# Arduino-Pro-Mini.net
KiCad netlist of a schematic drawn in EAGLE
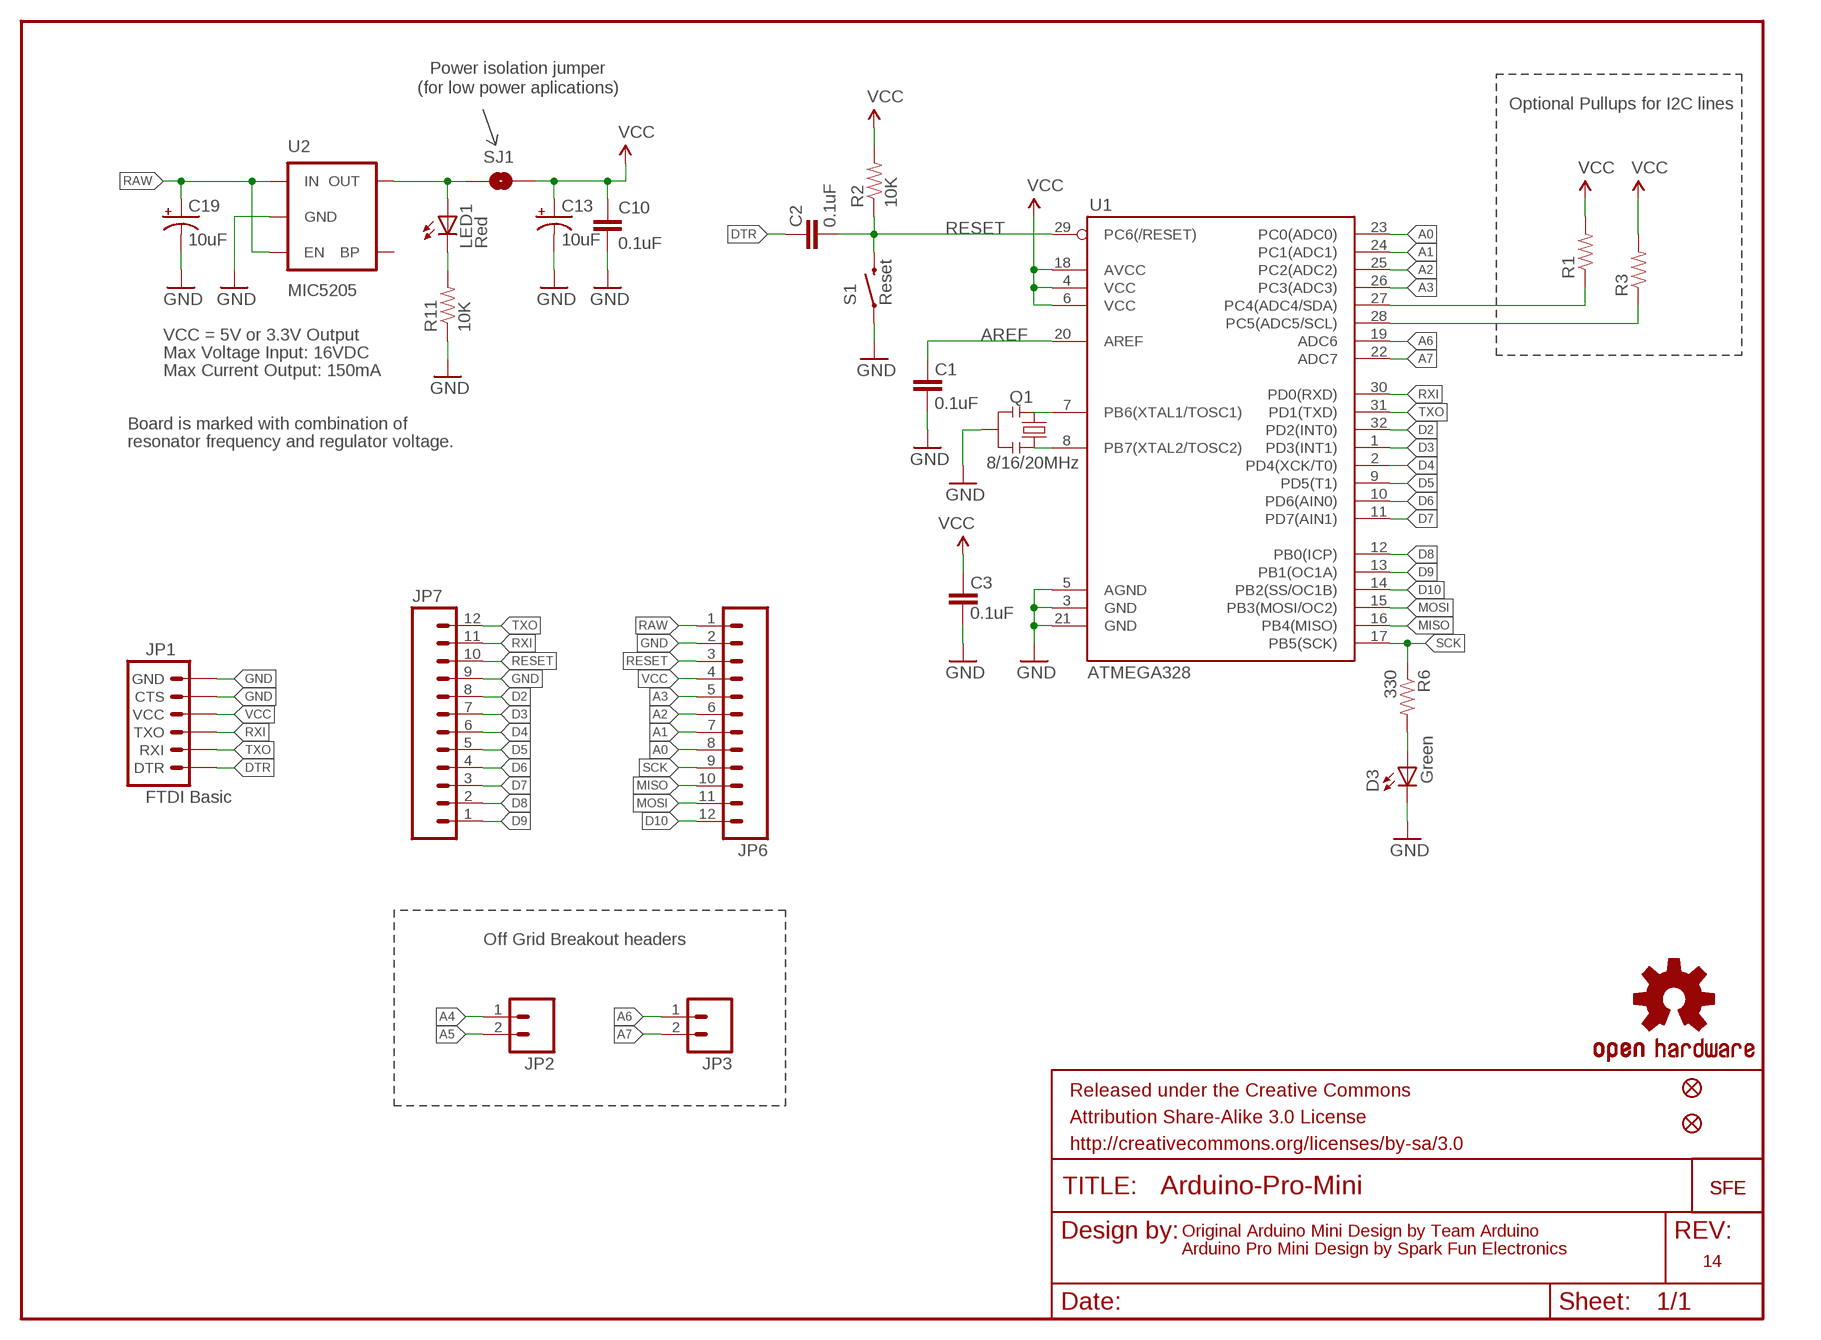
[diagram p0: schematic, sheet 1]

(export (version "E")
  (design (tool "Eeschema 10.0.6"))
  (components
    (comp (ref "C1")
      (value "0.1uF")
      (footprint "eagle-import:0603-CAP")
      (libsource (lib "eagle-import") (part "CAP0603-CAP"))
    )
    (comp (ref "C2")
      (value "0.1uF")
      (footprint "eagle-import:0603-CAP")
      (libsource (lib "eagle-import") (part "CAP0603-CAP"))
    )
    (comp (ref "C3")
      (value "0.1uF")
      (footprint "eagle-import:0603-CAP")
      (libsource (lib "eagle-import") (part "CAP0603-CAP"))
    )
    (comp (ref "C10")
      (value "0.1uF")
      (footprint "eagle-import:0603-CAP")
      (libsource (lib "eagle-import") (part "CAP0603-CAP"))
    )
    (comp (ref "C13")
      (value "10uF")
      (footprint "eagle-import:EIA3216")
      (libsource (lib "eagle-import") (part "CAP_POL1206"))
    )
    (comp (ref "C19")
      (value "10uF")
      (footprint "eagle-import:EIA3216")
      (libsource (lib "eagle-import") (part "CAP_POL1206"))
    )
    (comp (ref "D3")
      (value "Green")
      (footprint "eagle-import:0603-LED-ALT1")
      (libsource (lib "eagle-import") (part "LED"))
    )
    (comp (ref "FRAME1")
      (value "FRAME-LETTER")
      (footprint "eagle-import:CREATIVE_COMMONS")
      (libsource (lib "eagle-import") (part "FRAME-LETTER"))
    )
    (comp (ref "JP1")
      (value "FTDI Basic")
      (footprint "eagle-import:1X06")
      (libsource (lib "eagle-import") (part "ARDUINO_SERIAL_PROGRAMPTH"))
    )
    (comp (ref "JP2")
      (value "M02PTH")
      (footprint "eagle-import:1X02")
      (libsource (lib "eagle-import") (part "M02PTH"))
    )
    (comp (ref "JP3")
      (value "M02PTH")
      (footprint "eagle-import:1X02")
      (libsource (lib "eagle-import") (part "M02PTH"))
    )
    (comp (ref "JP5")
      (value "FIDUCIALUFIDUCIAL")
      (footprint "eagle-import:MICRO-FIDUCIAL")
      (libsource (lib "eagle-import") (part "FIDUCIALUFIDUCIAL"))
    )
    (comp (ref "JP6")
      (value "M12PTH")
      (footprint "eagle-import:1X12")
      (libsource (lib "eagle-import") (part "M12PTH"))
    )
    (comp (ref "JP7")
      (value "M12PTH")
      (footprint "eagle-import:1X12")
      (libsource (lib "eagle-import") (part "M12PTH"))
    )
    (comp (ref "JP8")
      (value "FIDUCIALUFIDUCIAL")
      (footprint "eagle-import:MICRO-FIDUCIAL")
      (libsource (lib "eagle-import") (part "FIDUCIALUFIDUCIAL"))
    )
    (comp (ref "LED1")
      (value "Red")
      (footprint "eagle-import:0603-LED-ALT1")
      (libsource (lib "eagle-import") (part "LED"))
    )
    (comp (ref "Q1")
      (value "8/16/20MHz")
      (footprint "eagle-import:RESONATOR-SMD-1_1")
      (libsource (lib "eagle-import") (part "RESONATOR1{colon}1"))
    )
    (comp (ref "R1")
      (value "RESISTOR0603-RES")
      (footprint "eagle-import:0603-RES")
      (libsource (lib "eagle-import") (part "RESISTOR0603-RES"))
    )
    (comp (ref "R2")
      (value "10K")
      (footprint "eagle-import:0603-RES")
      (libsource (lib "eagle-import") (part "RESISTOR0603-RES"))
    )
    (comp (ref "R3")
      (value "RESISTOR0603-RES")
      (footprint "eagle-import:0603-RES")
      (libsource (lib "eagle-import") (part "RESISTOR0603-RES"))
    )
    (comp (ref "R6")
      (value "330")
      (footprint "eagle-import:0603-RES")
      (libsource (lib "eagle-import") (part "RESISTOR0603-RES"))
    )
    (comp (ref "R11")
      (value "10K")
      (footprint "eagle-import:0603-RES")
      (libsource (lib "eagle-import") (part "RESISTOR0603-RES"))
    )
    (comp (ref "S1")
      (value "Reset")
      (footprint "eagle-import:TACTILE-SWITCH-SMD-ALT01")
      (libsource (lib "eagle-import") (part "SWITCH-MOMENTARY-2SMD-ALT01"))
    )
    (comp (ref "SJ1")
      (value "SOLDERJUMPERNC")
      (footprint "eagle-import:SJ_2S")
      (libsource (lib "eagle-import") (part "SOLDERJUMPERNC"))
    )
    (comp (ref "U$1")
      (value "LOGO-SFESK")
      (footprint "eagle-import:SFE-LOGO-FLAME")
      (libsource (lib "eagle-import") (part "LOGO-SFESK"))
    )
    (comp (ref "U$3")
      (value "OSHW-LOGOS")
      (footprint "eagle-import:OSHW-LOGO-S")
      (libsource (lib "eagle-import") (part "OSHW-LOGOS"))
    )
    (comp (ref "U$11")
      (value "LOGO-SFENEW")
      (footprint "eagle-import:SFE-NEW-WEBLOGO")
      (libsource (lib "eagle-import") (part "LOGO-SFENEW"))
    )
    (comp (ref "U1")
      (value "ATMEGA328")
      (footprint "eagle-import:TQFP32-08")
      (libsource (lib "eagle-import") (part "ATMEGA168"))
    )
    (comp (ref "U2")
      (value "MIC5205")
      (footprint "eagle-import:SOT23-5")
      (libsource (lib "eagle-import") (part "V_REG_LDOSMD"))
    )
  )
  (nets
    (net (code "1") (name "/AREF") (class "Default")
      (node (ref "C1") (pin "2") (pinfunction "2_2") (pintype "passive"))
      (node (ref "U1") (pin "20") (pinfunction "AREF_20") (pintype "bidirectional"))
    )
    (net (code "2") (name "A0") (class "Default")
      (node (ref "JP6") (pin "8") (pinfunction "8_8") (pintype "passive"))
      (node (ref "U1") (pin "23") (pinfunction "PC0(ADC0)_23") (pintype "bidirectional"))
    )
    (net (code "3") (name "A1") (class "Default")
      (node (ref "JP6") (pin "7") (pinfunction "7_7") (pintype "passive"))
      (node (ref "U1") (pin "24") (pinfunction "PC1(ADC1)_24") (pintype "bidirectional"))
    )
    (net (code "4") (name "A2") (class "Default")
      (node (ref "JP6") (pin "6") (pinfunction "6_6") (pintype "passive"))
      (node (ref "U1") (pin "25") (pinfunction "PC2(ADC2)_25") (pintype "bidirectional"))
    )
    (net (code "5") (name "A3") (class "Default")
      (node (ref "JP6") (pin "5") (pinfunction "5_5") (pintype "passive"))
      (node (ref "U1") (pin "26") (pinfunction "PC3(ADC3)_26") (pintype "bidirectional"))
    )
    (net (code "6") (name "A4") (class "Default")
      (node (ref "JP2") (pin "1") (pinfunction "1_1") (pintype "passive"))
      (node (ref "R1") (pin "1") (pinfunction "1_1") (pintype "passive"))
      (node (ref "U1") (pin "27") (pinfunction "PC4(ADC4/SDA)_27") (pintype "bidirectional"))
    )
    (net (code "7") (name "A5") (class "Default")
      (node (ref "JP2") (pin "2") (pinfunction "2_2") (pintype "passive"))
      (node (ref "R3") (pin "1") (pinfunction "1_1") (pintype "passive"))
      (node (ref "U1") (pin "28") (pinfunction "PC5(ADC5/SCL)_28") (pintype "bidirectional"))
    )
    (net (code "8") (name "A6") (class "Default")
      (node (ref "JP3") (pin "1") (pinfunction "1_1") (pintype "passive"))
      (node (ref "U1") (pin "19") (pinfunction "ADC6_19") (pintype "bidirectional"))
    )
    (net (code "9") (name "A7") (class "Default")
      (node (ref "JP3") (pin "2") (pinfunction "2_2") (pintype "passive"))
      (node (ref "U1") (pin "22") (pinfunction "ADC7_22") (pintype "bidirectional"))
    )
    (net (code "10") (name "D2") (class "Default")
      (node (ref "JP7") (pin "8") (pinfunction "8_8") (pintype "passive"))
      (node (ref "U1") (pin "32") (pinfunction "PD2(INT0)_32") (pintype "bidirectional"))
    )
    (net (code "11") (name "D3") (class "Default")
      (node (ref "JP7") (pin "7") (pinfunction "7_7") (pintype "passive"))
      (node (ref "U1") (pin "1") (pinfunction "PD3(INT1)_1") (pintype "bidirectional"))
    )
    (net (code "12") (name "D4") (class "Default")
      (node (ref "JP7") (pin "6") (pinfunction "6_6") (pintype "passive"))
      (node (ref "U1") (pin "2") (pinfunction "PD4(XCK/T0)_2") (pintype "bidirectional"))
    )
    (net (code "13") (name "D5") (class "Default")
      (node (ref "JP7") (pin "5") (pinfunction "5_5") (pintype "passive"))
      (node (ref "U1") (pin "9") (pinfunction "PD5(T1)_9") (pintype "bidirectional"))
    )
    (net (code "14") (name "D6") (class "Default")
      (node (ref "JP7") (pin "4") (pinfunction "4_4") (pintype "passive"))
      (node (ref "U1") (pin "10") (pinfunction "PD6(AIN0)_10") (pintype "bidirectional"))
    )
    (net (code "15") (name "D7") (class "Default")
      (node (ref "JP7") (pin "3") (pinfunction "3_3") (pintype "passive"))
      (node (ref "U1") (pin "11") (pinfunction "PD7(AIN1)_11") (pintype "bidirectional"))
    )
    (net (code "16") (name "D8") (class "Default")
      (node (ref "JP7") (pin "2") (pinfunction "2_2") (pintype "passive"))
      (node (ref "U1") (pin "12") (pinfunction "PB0(ICP)_12") (pintype "bidirectional"))
    )
    (net (code "17") (name "D9") (class "Default")
      (node (ref "JP7") (pin "1") (pinfunction "1_1") (pintype "passive"))
      (node (ref "U1") (pin "13") (pinfunction "PB1(OC1A)_13") (pintype "bidirectional"))
    )
    (net (code "18") (name "D10") (class "Default")
      (node (ref "JP6") (pin "12") (pinfunction "12_12") (pintype "passive"))
      (node (ref "U1") (pin "14") (pinfunction "PB2(SS/OC1B)_14") (pintype "bidirectional"))
    )
    (net (code "19") (name "DTR") (class "Default")
      (node (ref "C2") (pin "2") (pinfunction "2_2") (pintype "passive"))
      (node (ref "JP1") (pin "1") (pinfunction "DTR_1") (pintype "passive"))
    )
    (net (code "20") (name "GND") (class "Default")
      (node (ref "C1") (pin "1") (pinfunction "1_1") (pintype "passive"))
      (node (ref "C10") (pin "2") (pinfunction "2_2") (pintype "passive"))
      (node (ref "C13") (pin "C") (pinfunction "-_C") (pintype "passive"))
      (node (ref "C19") (pin "C") (pinfunction "-_C") (pintype "passive"))
      (node (ref "C3") (pin "1") (pinfunction "1_1") (pintype "passive"))
      (node (ref "D3") (pin "C") (pinfunction "C_C") (pintype "passive"))
      (node (ref "JP1") (pin "5") (pinfunction "CTS_5") (pintype "passive"))
      (node (ref "JP1") (pin "6") (pinfunction "GND_6") (pintype "passive"))
      (node (ref "JP6") (pin "2") (pinfunction "2_2") (pintype "passive"))
      (node (ref "JP7") (pin "9") (pinfunction "9_9") (pintype "passive"))
      (node (ref "Q1") (pin "2") (pinfunction "2_2") (pintype "passive"))
      (node (ref "R11") (pin "1") (pinfunction "1_1") (pintype "passive"))
      (node (ref "S1") (pin "1") (pinfunction "1_1") (pintype "passive"))
      (node (ref "S1") (pin "2") (pinfunction "1_2") (pintype "passive"))
      (node (ref "U1") (pin "21") (pinfunction "GND_21") (pintype "bidirectional"))
      (node (ref "U1") (pin "3") (pinfunction "GND_3") (pintype "bidirectional"))
      (node (ref "U1") (pin "5") (pinfunction "AGND_5") (pintype "bidirectional"))
      (node (ref "U2") (pin "2") (pinfunction "GND_2") (pintype "input"))
    )
    (net (code "21") (name "MISO") (class "Default")
      (node (ref "JP6") (pin "10") (pinfunction "10_10") (pintype "passive"))
      (node (ref "U1") (pin "16") (pinfunction "PB4(MISO)_16") (pintype "bidirectional"))
    )
    (net (code "22") (name "MOSI") (class "Default")
      (node (ref "JP6") (pin "11") (pinfunction "11_11") (pintype "passive"))
      (node (ref "U1") (pin "15") (pinfunction "PB3(MOSI/OC2)_15") (pintype "bidirectional"))
    )
    (net (code "23") (name "Net-(D3-PadA)") (class "Default")
      (node (ref "D3") (pin "A") (pinfunction "A_A") (pintype "passive"))
      (node (ref "R6") (pin "2") (pinfunction "2_2") (pintype "passive"))
    )
    (net (code "24") (name "Net-(LED1-PadC)") (class "Default")
      (node (ref "LED1") (pin "C") (pinfunction "C_C") (pintype "passive"))
      (node (ref "R11") (pin "2") (pinfunction "2_2") (pintype "passive"))
    )
    (net (code "25") (name "Net-(U1-PB6(XTAL1{slash}TOSC1))") (class "Default")
      (node (ref "Q1") (pin "1") (pinfunction "1_1") (pintype "passive"))
      (node (ref "U1") (pin "7") (pinfunction "PB6(XTAL1/TOSC1)_7") (pintype "bidirectional"))
    )
    (net (code "26") (name "Net-(U1-PB7(XTAL2{slash}TOSC2))") (class "Default")
      (node (ref "Q1") (pin "3") (pinfunction "3_3") (pintype "passive"))
      (node (ref "U1") (pin "8") (pinfunction "PB7(XTAL2/TOSC2)_8") (pintype "bidirectional"))
    )
    (net (code "27") (name "Net-(U2-OUT)") (class "Default")
      (node (ref "LED1") (pin "A") (pinfunction "A_A") (pintype "passive"))
      (node (ref "SJ1") (pin "1") (pinfunction "1_1") (pintype "passive"))
      (node (ref "U2") (pin "5") (pinfunction "OUT_5") (pintype "passive"))
    )
    (net (code "28") (name "RAW") (class "Default")
      (node (ref "C19") (pin "A") (pinfunction "+_A") (pintype "passive"))
      (node (ref "JP6") (pin "1") (pinfunction "1_1") (pintype "passive"))
      (node (ref "U2") (pin "1") (pinfunction "IN_1") (pintype "input"))
      (node (ref "U2") (pin "3") (pinfunction "EN_3") (pintype "input"))
    )
    (net (code "29") (name "RESET") (class "Default")
      (node (ref "C2") (pin "1") (pinfunction "1_1") (pintype "passive"))
      (node (ref "JP6") (pin "3") (pinfunction "3_3") (pintype "passive"))
      (node (ref "JP7") (pin "10") (pinfunction "10_10") (pintype "passive"))
      (node (ref "R2") (pin "1") (pinfunction "1_1") (pintype "passive"))
      (node (ref "S1") (pin "3") (pinfunction "2_3") (pintype "passive"))
      (node (ref "S1") (pin "4") (pinfunction "2_4") (pintype "passive"))
      (node (ref "U1") (pin "29") (pinfunction "PC6(/RESET)_29") (pintype "bidirectional"))
    )
    (net (code "30") (name "RXI") (class "Default")
      (node (ref "JP1") (pin "3") (pinfunction "TXO_3") (pintype "passive"))
      (node (ref "JP7") (pin "11") (pinfunction "11_11") (pintype "passive"))
      (node (ref "U1") (pin "30") (pinfunction "PD0(RXD)_30") (pintype "bidirectional"))
    )
    (net (code "31") (name "SCK") (class "Default")
      (node (ref "JP6") (pin "9") (pinfunction "9_9") (pintype "passive"))
      (node (ref "R6") (pin "1") (pinfunction "1_1") (pintype "passive"))
      (node (ref "U1") (pin "17") (pinfunction "PB5(SCK)_17") (pintype "bidirectional"))
    )
    (net (code "32") (name "TXO") (class "Default")
      (node (ref "JP1") (pin "2") (pinfunction "RXI_2") (pintype "passive"))
      (node (ref "JP7") (pin "12") (pinfunction "12_12") (pintype "passive"))
      (node (ref "U1") (pin "31") (pinfunction "PD1(TXD)_31") (pintype "bidirectional"))
    )
    (net (code "33") (name "VCC") (class "Default")
      (node (ref "C10") (pin "1") (pinfunction "1_1") (pintype "passive"))
      (node (ref "C13") (pin "A") (pinfunction "+_A") (pintype "passive"))
      (node (ref "C3") (pin "2") (pinfunction "2_2") (pintype "passive"))
      (node (ref "JP1") (pin "4") (pinfunction "VCC_4") (pintype "passive"))
      (node (ref "JP6") (pin "4") (pinfunction "4_4") (pintype "passive"))
      (node (ref "R1") (pin "2") (pinfunction "2_2") (pintype "passive"))
      (node (ref "R2") (pin "2") (pinfunction "2_2") (pintype "passive"))
      (node (ref "R3") (pin "2") (pinfunction "2_2") (pintype "passive"))
      (node (ref "SJ1") (pin "2") (pinfunction "2_2") (pintype "passive"))
      (node (ref "U1") (pin "18") (pinfunction "AVCC_18") (pintype "bidirectional"))
      (node (ref "U1") (pin "4") (pinfunction "VCC_4") (pintype "bidirectional"))
      (node (ref "U1") (pin "6") (pinfunction "VCC_6") (pintype "bidirectional"))
    )
    (net (code "34") (name "unconnected-(U2-BP-Pad4)") (class "Default")
      (node (ref "U2") (pin "4") (pinfunction "BP_4") (pintype "input"))
    )
  )
)
